# Fused_Inputs.net
KiCad netlist of a schematic drawn in Altium Designer
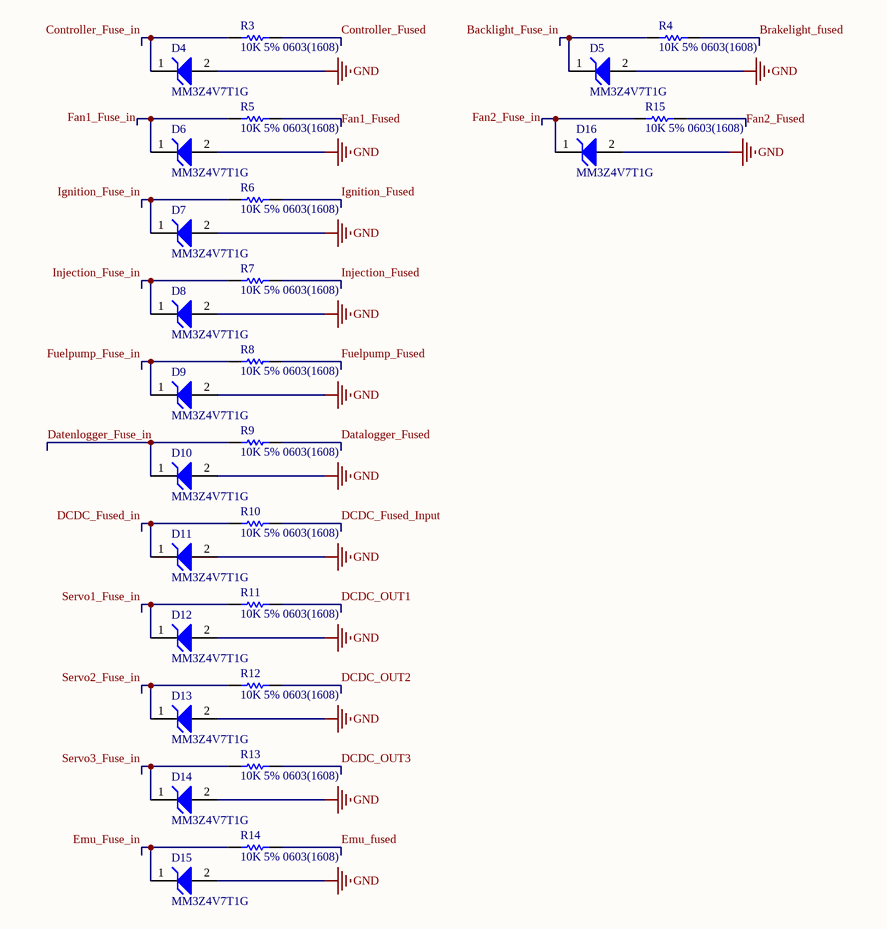
[diagram p0: Fused_Inputs.SchDoc]

(export (version "E")
  (design (tool "Eeschema 10.0.6"))
  (components
    (comp (ref "D4")
      (value "MM3Z4V7T1G")
      (footprint "ONSC-SOD-323-2-477-02_V")
      (description "Zener Voltage Regulator, 300 mW, 2-Pin SOD-323, Pb-Free, Tape and Reel")
      (fields (field (name "MANUFACTURER") "On Semiconductor"))
      (libsource (lib "Altium Content Vault") (part "ONSC-K1A2-2"))
    )
    (comp (ref "D5")
      (value "MM3Z4V7T1G")
      (footprint "ONSC-SOD-323-2-477-02_V")
      (description "Zener Voltage Regulator, 300 mW, 2-Pin SOD-323, Pb-Free, Tape and Reel")
      (fields (field (name "MANUFACTURER") "On Semiconductor"))
      (libsource (lib "Altium Content Vault") (part "ONSC-K1A2-2"))
    )
    (comp (ref "D6")
      (value "MM3Z4V7T1G")
      (footprint "ONSC-SOD-323-2-477-02_V")
      (description "Zener Voltage Regulator, 300 mW, 2-Pin SOD-323, Pb-Free, Tape and Reel")
      (fields (field (name "MANUFACTURER") "On Semiconductor"))
      (libsource (lib "Altium Content Vault") (part "ONSC-K1A2-2"))
    )
    (comp (ref "D7")
      (value "MM3Z4V7T1G")
      (footprint "ONSC-SOD-323-2-477-02_V")
      (description "Zener Voltage Regulator, 300 mW, 2-Pin SOD-323, Pb-Free, Tape and Reel")
      (fields (field (name "MANUFACTURER") "On Semiconductor"))
      (libsource (lib "Altium Content Vault") (part "ONSC-K1A2-2"))
    )
    (comp (ref "D8")
      (value "MM3Z4V7T1G")
      (footprint "ONSC-SOD-323-2-477-02_V")
      (description "Zener Voltage Regulator, 300 mW, 2-Pin SOD-323, Pb-Free, Tape and Reel")
      (fields (field (name "MANUFACTURER") "On Semiconductor"))
      (libsource (lib "Altium Content Vault") (part "ONSC-K1A2-2"))
    )
    (comp (ref "D9")
      (value "MM3Z4V7T1G")
      (footprint "ONSC-SOD-323-2-477-02_V")
      (description "Zener Voltage Regulator, 300 mW, 2-Pin SOD-323, Pb-Free, Tape and Reel")
      (fields (field (name "MANUFACTURER") "On Semiconductor"))
      (libsource (lib "Altium Content Vault") (part "ONSC-K1A2-2"))
    )
    (comp (ref "D10")
      (value "MM3Z4V7T1G")
      (footprint "ONSC-SOD-323-2-477-02_V")
      (description "Zener Voltage Regulator, 300 mW, 2-Pin SOD-323, Pb-Free, Tape and Reel")
      (fields (field (name "MANUFACTURER") "On Semiconductor"))
      (libsource (lib "Altium Content Vault") (part "ONSC-K1A2-2"))
    )
    (comp (ref "D11")
      (value "MM3Z4V7T1G")
      (footprint "ONSC-SOD-323-2-477-02_V")
      (description "Zener Voltage Regulator, 300 mW, 2-Pin SOD-323, Pb-Free, Tape and Reel")
      (fields (field (name "MANUFACTURER") "On Semiconductor"))
      (libsource (lib "Altium Content Vault") (part "ONSC-K1A2-2"))
    )
    (comp (ref "D12")
      (value "MM3Z4V7T1G")
      (footprint "ONSC-SOD-323-2-477-02_V")
      (description "Zener Voltage Regulator, 300 mW, 2-Pin SOD-323, Pb-Free, Tape and Reel")
      (fields (field (name "MANUFACTURER") "On Semiconductor"))
      (libsource (lib "Altium Content Vault") (part "ONSC-K1A2-2"))
    )
    (comp (ref "D13")
      (value "MM3Z4V7T1G")
      (footprint "ONSC-SOD-323-2-477-02_V")
      (description "Zener Voltage Regulator, 300 mW, 2-Pin SOD-323, Pb-Free, Tape and Reel")
      (fields (field (name "MANUFACTURER") "On Semiconductor"))
      (libsource (lib "Altium Content Vault") (part "ONSC-K1A2-2"))
    )
    (comp (ref "D14")
      (value "MM3Z4V7T1G")
      (footprint "ONSC-SOD-323-2-477-02_V")
      (description "Zener Voltage Regulator, 300 mW, 2-Pin SOD-323, Pb-Free, Tape and Reel")
      (fields (field (name "MANUFACTURER") "On Semiconductor"))
      (libsource (lib "Altium Content Vault") (part "ONSC-K1A2-2"))
    )
    (comp (ref "D15")
      (value "MM3Z4V7T1G")
      (footprint "ONSC-SOD-323-2-477-02_V")
      (description "Zener Voltage Regulator, 300 mW, 2-Pin SOD-323, Pb-Free, Tape and Reel")
      (fields (field (name "MANUFACTURER") "On Semiconductor"))
      (libsource (lib "Altium Content Vault") (part "ONSC-K1A2-2"))
    )
    (comp (ref "D16")
      (value "MM3Z4V7T1G")
      (footprint "ONSC-SOD-323-2-477-02_V")
      (description "Zener Voltage Regulator, 300 mW, 2-Pin SOD-323, Pb-Free, Tape and Reel")
      (fields (field (name "MANUFACTURER") "On Semiconductor"))
      (libsource (lib "Altium Content Vault") (part "ONSC-K1A2-2"))
    )
    (comp (ref "R3")
      (value "10K 5% 0603(1608)")
      (footprint "RESC0603(1608)_N")
      (description "10K 0.1W 5% 0603 (1608 Metric)  SMD")
      (fields (field (name "TOLERANCE") "5 %") (field (name "POWER") "0.1 W"))
      (libsource (lib "Altium Content Vault") (part "RES"))
    )
    (comp (ref "R4")
      (value "10K 5% 0603(1608)")
      (footprint "RESC0603(1608)_N")
      (description "10K 0.1W 5% 0603 (1608 Metric)  SMD")
      (fields (field (name "TOLERANCE") "5 %") (field (name "POWER") "0.1 W"))
      (libsource (lib "Altium Content Vault") (part "RES"))
    )
    (comp (ref "R5")
      (value "10K 5% 0603(1608)")
      (footprint "RESC0603(1608)_N")
      (description "10K 0.1W 5% 0603 (1608 Metric)  SMD")
      (fields (field (name "TOLERANCE") "5 %") (field (name "POWER") "0.1 W"))
      (libsource (lib "Altium Content Vault") (part "RES"))
    )
    (comp (ref "R6")
      (value "10K 5% 0603(1608)")
      (footprint "RESC0603(1608)_N")
      (description "10K 0.1W 5% 0603 (1608 Metric)  SMD")
      (fields (field (name "TOLERANCE") "5 %") (field (name "POWER") "0.1 W"))
      (libsource (lib "Altium Content Vault") (part "RES"))
    )
    (comp (ref "R7")
      (value "10K 5% 0603(1608)")
      (footprint "RESC0603(1608)_N")
      (description "10K 0.1W 5% 0603 (1608 Metric)  SMD")
      (fields (field (name "TOLERANCE") "5 %") (field (name "POWER") "0.1 W"))
      (libsource (lib "Altium Content Vault") (part "RES"))
    )
    (comp (ref "R8")
      (value "10K 5% 0603(1608)")
      (footprint "RESC0603(1608)_N")
      (description "10K 0.1W 5% 0603 (1608 Metric)  SMD")
      (fields (field (name "TOLERANCE") "5 %") (field (name "POWER") "0.1 W"))
      (libsource (lib "Altium Content Vault") (part "RES"))
    )
    (comp (ref "R9")
      (value "10K 5% 0603(1608)")
      (footprint "RESC0603(1608)_N")
      (description "10K 0.1W 5% 0603 (1608 Metric)  SMD")
      (fields (field (name "TOLERANCE") "5 %") (field (name "POWER") "0.1 W"))
      (libsource (lib "Altium Content Vault") (part "RES"))
    )
    (comp (ref "R10")
      (value "10K 5% 0603(1608)")
      (footprint "RESC0603(1608)_N")
      (description "10K 0.1W 5% 0603 (1608 Metric)  SMD")
      (fields (field (name "TOLERANCE") "5 %") (field (name "POWER") "0.1 W"))
      (libsource (lib "Altium Content Vault") (part "RES"))
    )
    (comp (ref "R11")
      (value "10K 5% 0603(1608)")
      (footprint "RESC0603(1608)_N")
      (description "10K 0.1W 5% 0603 (1608 Metric)  SMD")
      (fields (field (name "TOLERANCE") "5 %") (field (name "POWER") "0.1 W"))
      (libsource (lib "Altium Content Vault") (part "RES"))
    )
    (comp (ref "R12")
      (value "10K 5% 0603(1608)")
      (footprint "RESC0603(1608)_N")
      (description "10K 0.1W 5% 0603 (1608 Metric)  SMD")
      (fields (field (name "TOLERANCE") "5 %") (field (name "POWER") "0.1 W"))
      (libsource (lib "Altium Content Vault") (part "RES"))
    )
    (comp (ref "R13")
      (value "10K 5% 0603(1608)")
      (footprint "RESC0603(1608)_N")
      (description "10K 0.1W 5% 0603 (1608 Metric)  SMD")
      (fields (field (name "TOLERANCE") "5 %") (field (name "POWER") "0.1 W"))
      (libsource (lib "Altium Content Vault") (part "RES"))
    )
    (comp (ref "R14")
      (value "10K 5% 0603(1608)")
      (footprint "RESC0603(1608)_N")
      (description "10K 0.1W 5% 0603 (1608 Metric)  SMD")
      (fields (field (name "TOLERANCE") "5 %") (field (name "POWER") "0.1 W"))
      (libsource (lib "Altium Content Vault") (part "RES"))
    )
    (comp (ref "R15")
      (value "10K 5% 0603(1608)")
      (footprint "RESC0603(1608)_N")
      (description "10K 0.1W 5% 0603 (1608 Metric)  SMD")
      (fields (field (name "TOLERANCE") "5 %") (field (name "POWER") "0.1 W"))
      (libsource (lib "Altium Content Vault") (part "RES"))
    )
  )
  (nets
    (net (code "1") (name "/Backlight_Fuse_in") (class "Default")
      (node (ref "D5") (pin "1") (pinfunction "K_1") (pintype "passive"))
      (node (ref "R4") (pin "1") (pinfunction "1_1") (pintype "passive"))
    )
    (net (code "2") (name "/Brakelight_fused") (class "Default")
      (node (ref "R4") (pin "2") (pinfunction "2_2") (pintype "passive"))
    )
    (net (code "3") (name "/Controller_Fuse_in") (class "Default")
      (node (ref "D4") (pin "1") (pinfunction "K_1") (pintype "passive"))
      (node (ref "R3") (pin "1") (pinfunction "1_1") (pintype "passive"))
    )
    (net (code "4") (name "/Controller_Fused") (class "Default")
      (node (ref "R3") (pin "2") (pinfunction "2_2") (pintype "passive"))
    )
    (net (code "5") (name "/DCDC_Fused_Input") (class "Default")
      (node (ref "R10") (pin "2") (pinfunction "2_2") (pintype "passive"))
    )
    (net (code "6") (name "/DCDC_Fused_in") (class "Default")
      (node (ref "D11") (pin "1") (pinfunction "K_1") (pintype "passive"))
      (node (ref "R10") (pin "1") (pinfunction "1_1") (pintype "passive"))
    )
    (net (code "7") (name "/DCDC_OUT1") (class "Default")
      (node (ref "R11") (pin "2") (pinfunction "2_2") (pintype "passive"))
    )
    (net (code "8") (name "/DCDC_OUT2") (class "Default")
      (node (ref "R12") (pin "2") (pinfunction "2_2") (pintype "passive"))
    )
    (net (code "9") (name "/DCDC_OUT3") (class "Default")
      (node (ref "R13") (pin "2") (pinfunction "2_2") (pintype "passive"))
    )
    (net (code "10") (name "/Datalogger_Fused") (class "Default")
      (node (ref "R9") (pin "2") (pinfunction "2_2") (pintype "passive"))
    )
    (net (code "11") (name "/Datenlogger_Fuse_in") (class "Default")
      (node (ref "D10") (pin "1") (pinfunction "K_1") (pintype "passive"))
      (node (ref "R9") (pin "1") (pinfunction "1_1") (pintype "passive"))
    )
    (net (code "12") (name "/Emu_Fuse_in") (class "Default")
      (node (ref "D15") (pin "1") (pinfunction "K_1") (pintype "passive"))
      (node (ref "R14") (pin "1") (pinfunction "1_1") (pintype "passive"))
    )
    (net (code "13") (name "/Emu_fused") (class "Default")
      (node (ref "R14") (pin "2") (pinfunction "2_2") (pintype "passive"))
    )
    (net (code "14") (name "/Fan1_Fuse_in") (class "Default")
      (node (ref "D6") (pin "1") (pinfunction "K_1") (pintype "passive"))
      (node (ref "R5") (pin "1") (pinfunction "1_1") (pintype "passive"))
    )
    (net (code "15") (name "/Fan1_Fused") (class "Default")
      (node (ref "R5") (pin "2") (pinfunction "2_2") (pintype "passive"))
    )
    (net (code "16") (name "/Fan2_Fuse_in") (class "Default")
      (node (ref "D16") (pin "1") (pinfunction "K_1") (pintype "passive"))
      (node (ref "R15") (pin "1") (pinfunction "1_1") (pintype "passive"))
    )
    (net (code "17") (name "/Fan2_Fused") (class "Default")
      (node (ref "R15") (pin "2") (pinfunction "2_2") (pintype "passive"))
    )
    (net (code "18") (name "/Fuelpump_Fuse_in") (class "Default")
      (node (ref "D9") (pin "1") (pinfunction "K_1") (pintype "passive"))
      (node (ref "R8") (pin "1") (pinfunction "1_1") (pintype "passive"))
    )
    (net (code "19") (name "/Fuelpump_Fused") (class "Default")
      (node (ref "R8") (pin "2") (pinfunction "2_2") (pintype "passive"))
    )
    (net (code "20") (name "/Ignition_Fuse_in") (class "Default")
      (node (ref "D7") (pin "1") (pinfunction "K_1") (pintype "passive"))
      (node (ref "R6") (pin "1") (pinfunction "1_1") (pintype "passive"))
    )
    (net (code "21") (name "/Ignition_Fused") (class "Default")
      (node (ref "R6") (pin "2") (pinfunction "2_2") (pintype "passive"))
    )
    (net (code "22") (name "/Injection_Fuse_in") (class "Default")
      (node (ref "D8") (pin "1") (pinfunction "K_1") (pintype "passive"))
      (node (ref "R7") (pin "1") (pinfunction "1_1") (pintype "passive"))
    )
    (net (code "23") (name "/Injection_Fused") (class "Default")
      (node (ref "R7") (pin "2") (pinfunction "2_2") (pintype "passive"))
    )
    (net (code "24") (name "/Servo1_Fuse_in") (class "Default")
      (node (ref "D12") (pin "1") (pinfunction "K_1") (pintype "passive"))
      (node (ref "R11") (pin "1") (pinfunction "1_1") (pintype "passive"))
    )
    (net (code "25") (name "/Servo2_Fuse_in") (class "Default")
      (node (ref "D13") (pin "1") (pinfunction "K_1") (pintype "passive"))
      (node (ref "R12") (pin "1") (pinfunction "1_1") (pintype "passive"))
    )
    (net (code "26") (name "/Servo3_Fuse_in") (class "Default")
      (node (ref "D14") (pin "1") (pinfunction "K_1") (pintype "passive"))
      (node (ref "R13") (pin "1") (pinfunction "1_1") (pintype "passive"))
    )
    (net (code "27") (name "GND") (class "Default")
      (node (ref "D10") (pin "2") (pinfunction "A_2") (pintype "passive"))
      (node (ref "D11") (pin "2") (pinfunction "A_2") (pintype "passive"))
      (node (ref "D12") (pin "2") (pinfunction "A_2") (pintype "passive"))
      (node (ref "D13") (pin "2") (pinfunction "A_2") (pintype "passive"))
      (node (ref "D14") (pin "2") (pinfunction "A_2") (pintype "passive"))
      (node (ref "D15") (pin "2") (pinfunction "A_2") (pintype "passive"))
      (node (ref "D16") (pin "2") (pinfunction "A_2") (pintype "passive"))
      (node (ref "D4") (pin "2") (pinfunction "A_2") (pintype "passive"))
      (node (ref "D5") (pin "2") (pinfunction "A_2") (pintype "passive"))
      (node (ref "D6") (pin "2") (pinfunction "A_2") (pintype "passive"))
      (node (ref "D7") (pin "2") (pinfunction "A_2") (pintype "passive"))
      (node (ref "D8") (pin "2") (pinfunction "A_2") (pintype "passive"))
      (node (ref "D9") (pin "2") (pinfunction "A_2") (pintype "passive"))
    )
  )
)
